# 1_Power.net
KiCad netlist of a schematic drawn in Altium Designer
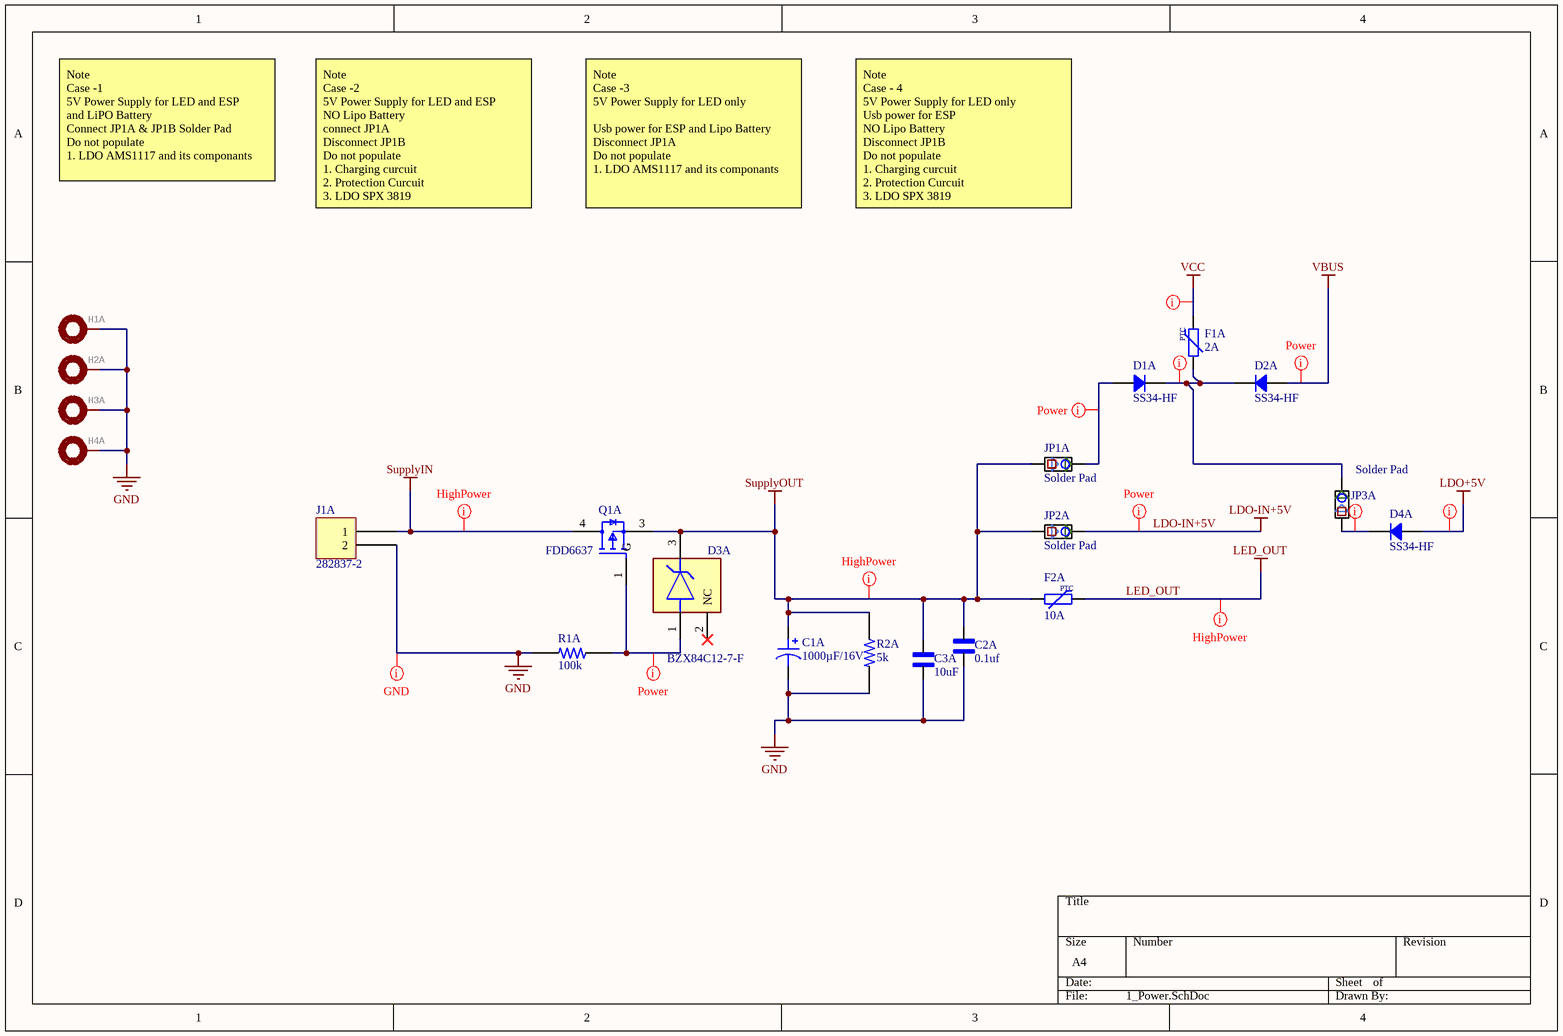
[diagram p0: 1_Power.SchDoc]

(export (version "E")
  (design (tool "Eeschema 10.0.6"))
  (components
    (comp (ref "C1A")
      (value "1000µF/16V")
      (footprint "CAP TH ALUM ELEC D10.00mm S5.00mm H17.50mm")
      (description "AL LYTIC, RADIAL, 16VDC, 1000UF")
      (fields
        (field (name "PART NUMBER") "EEU-FK1C102")
        (field (name "MANUFACTURER") "Panasonic Electronic Components")
      )
      (libsource (lib "ESP-12F_WLED_IOT_LIPO") (part "Polarised Capacitor"))
    )
    (comp (ref "C2A")
      (value "0.1uf")
      (footprint "C-0603")
      (description "Ceramic Capacitor 16V 0603 (1608 Metric)")
      (fields (field (name "MP") "C0603C104J4RAC") (field (name "MF") "KEMET"))
      (libsource (lib "ESP-12F_WLED_IOT_LIPO") (part "C-0603"))
    )
    (comp (ref "C3A")
      (value "10uF")
      (footprint "C-0603")
      (description "Ceramic Capacitor 16V 0603 (1608 Metric)")
      (fields (field (name "MP") "C0603C104J4RAC") (field (name "MF") "KEMET"))
      (libsource (lib "ESP-12F_WLED_IOT_LIPO") (part "C-0603"))
    )
    (comp (ref "D1A")
      (value "SS34-HF")
      (footprint "DO214AC SMA")
      (description "DIODE SCHOTTKY 40V 3A DO214AC")
      (fields (field (name "MANUFACTURER") "Comchip Technology"))
      (libsource (lib "ESP-12F_WLED_IOT_LIPO") (part "Diode"))
    )
    (comp (ref "D2A")
      (value "SS34-HF")
      (footprint "DO214AC SMA")
      (description "DIODE SCHOTTKY 40V 3A DO214AC")
      (fields (field (name "MANUFACTURER") "Comchip Technology"))
      (libsource (lib "ESP-12F_WLED_IOT_LIPO") (part "Diode"))
    )
    (comp (ref "D3A")
      (value "BZX84C12-7-F")
      (footprint "FP-SOT23-MFG")
      (description "DIODE ZENER 12V 300MW SOT23-3")
      (fields
        (field (name "OCTOPART") "https://octopart.com/bzx84c12-7-f-diodes+inc.-327696")
        (field (name "MANUFACTURER") "Diodes Inc.")
      )
      (libsource (lib "ESP-12F_WLED_IOT_LIPO") (part "4a6bcd6c75a58f30e1c7f5dd6419ea8"))
    )
    (comp (ref "D4A")
      (value "SS34-HF")
      (footprint "DO214AC SMA")
      (description "DIODE SCHOTTKY 40V 3A DO214AC")
      (fields (field (name "MANUFACTURER") "Comchip Technology"))
      (libsource (lib "ESP-12F_WLED_IOT_LIPO") (part "Diode"))
    )
    (comp (ref "F1A")
      (value "2A")
      (footprint "FUSE_1206")
      (description "Fuse PPTC SMD 1206")
      (libsource (lib "ESP-12F_WLED_IOT_LIPO") (part "FUSE_PPTC_1206"))
    )
    (comp (ref "F2A")
      (value "10A")
      (footprint "FUSE_1206")
      (description "Fuse PPTC SMD 1206")
      (libsource (lib "ESP-12F_WLED_IOT_LIPO") (part "FUSE_PPTC_1206"))
    )
    (comp (ref "H1A")
      (value "MOUNTING PAD, round")
      (footprint "2,4-PAD")
      (libsource (lib "ESP-12F_WLED_IOT_LIPO") (part "MOUNT-PAD-ROUND2.4"))
    )
    (comp (ref "H2A")
      (value "MOUNTING PAD, round")
      (footprint "2,4-PAD")
      (libsource (lib "ESP-12F_WLED_IOT_LIPO") (part "MOUNT-PAD-ROUND2.4"))
    )
    (comp (ref "H3A")
      (value "MOUNTING PAD, round")
      (footprint "2,4-PAD")
      (libsource (lib "ESP-12F_WLED_IOT_LIPO") (part "MOUNT-PAD-ROUND2.4"))
    )
    (comp (ref "H4A")
      (value "MOUNTING PAD, round")
      (footprint "2,4-PAD")
      (libsource (lib "ESP-12F_WLED_IOT_LIPO") (part "MOUNT-PAD-ROUND2.4"))
    )
    (comp (ref "J1A")
      (value "282837-2")
      (footprint "TE 282837-2")
      (description "TERM BLK 2P SIDE ENT 5.08MM PCB")
      (fields (field (name "MANUFACTURER") "TE Connectivity AMP Connectors") (field (name "VOLTAGE") "300 V"))
      (libsource (lib "ESP-12F_WLED_IOT_LIPO") (part "2 Pin"))
    )
    (comp (ref "JP1A")
      (value "Solder Pad")
      (footprint "Solder_Pad_2_Pin_NC_Medium")
      (description "Solder Pad 2 Pin NC 1.016 mm Pitch")
      (libsource (lib "ESP-12F_WLED_IOT_LIPO") (part "Solder_Pad_2_Pin_NC_Medium"))
    )
    (comp (ref "JP2A")
      (value "Solder Pad")
      (footprint "Solder_Pad_2_Pin_NC_Medium")
      (description "Solder Pad 2 Pin NC 1.016 mm Pitch")
      (libsource (lib "ESP-12F_WLED_IOT_LIPO") (part "Solder_Pad_2_Pin_NC_Medium"))
    )
    (comp (ref "JP3A")
      (value "Solder Pad")
      (footprint "Solder_Pad_2_Pin_NC_Medium")
      (description "Solder Pad 2 Pin NC 1.016 mm Pitch")
      (libsource (lib "ESP-12F_WLED_IOT_LIPO") (part "Solder_Pad_2_Pin_NC_Medium"))
    )
    (comp (ref "Q1A")
      (value "FDD6637")
      (footprint "FP-369AS-MFG")
      (description "MOSFET P-CH 35V 13A DPAK")
      (fields
        (field (name "OCTOPART") "https://octopart.com/fdd6637-on+semiconductor-84325825")
        (field (name "MANUFACTURER") "ON Semiconductor")
      )
      (libsource (lib "ESP-12F_WLED_IOT_LIPO") (part "cee2e0b37b8b7601ebfb19aba2d2b4e"))
    )
    (comp (ref "R1A")
      (value "100k")
      (footprint "R-0603")
      (description "0603")
      (fields (field (name "MP") "2-1623703-0") (field (name "TOLERANCE") "1%"))
      (libsource (lib "ESP-12F_WLED_IOT_LIPO") (part "R-0603"))
    )
    (comp (ref "R2A")
      (value "5k")
      (footprint "R-0603")
      (description "0603")
      (fields (field (name "MP") "2-1623703-0") (field (name "TOLERANCE") "1%"))
      (libsource (lib "ESP-12F_WLED_IOT_LIPO") (part "R-0603"))
    )
  )
  (nets
    (net (code "1") (name "GND") (class "Default")
      (node (ref "C1A") (pin "2") (pinfunction "2_2") (pintype "passive"))
      (node (ref "C2A") (pin "1") (pinfunction "1_1") (pintype "passive"))
      (node (ref "C3A") (pin "1") (pinfunction "1_1") (pintype "passive"))
      (node (ref "H1A") (pin "1") (pinfunction "MOUNT_1") (pintype "passive"))
      (node (ref "H2A") (pin "1") (pinfunction "MOUNT_1") (pintype "passive"))
      (node (ref "H3A") (pin "1") (pinfunction "MOUNT_1") (pintype "passive"))
      (node (ref "H4A") (pin "1") (pinfunction "MOUNT_1") (pintype "passive"))
      (node (ref "J1A") (pin "2") (pinfunction "2_2") (pintype "passive"))
      (node (ref "R1A") (pin "2") (pinfunction "2_2") (pintype "passive"))
      (node (ref "R2A") (pin "2") (pinfunction "2_2") (pintype "passive"))
    )
    (net (code "2") (name "LDO+5V") (class "Default")
      (node (ref "D4A") (pin "1") (pinfunction "1_1") (pintype "passive"))
    )
    (net (code "3") (name "LDO-IN+5V") (class "Default")
      (node (ref "JP2A") (pin "2") (pinfunction "2_2") (pintype "passive"))
    )
    (net (code "4") (name "LED_OUT") (class "Default")
      (node (ref "F2A") (pin "2") (pinfunction "2_2") (pintype "passive"))
    )
    (net (code "5") (name "Net-(D1A-Pad1)") (class "Default")
      (node (ref "D1A") (pin "1") (pinfunction "1_1") (pintype "passive"))
      (node (ref "JP1A") (pin "2") (pinfunction "2_2") (pintype "passive"))
    )
    (net (code "6") (name "Net-(D1A-Pad2)") (class "Default")
      (node (ref "D1A") (pin "2") (pinfunction "2_2") (pintype "passive"))
      (node (ref "D2A") (pin "2") (pinfunction "2_2") (pintype "passive"))
      (node (ref "F1A") (pin "1") (pinfunction "1_1") (pintype "passive"))
      (node (ref "JP3A") (pin "2") (pinfunction "2_2") (pintype "passive"))
    )
    (net (code "7") (name "Net-(D3A-A)") (class "Default")
      (node (ref "D3A") (pin "1") (pinfunction "A_1") (pintype "passive"))
      (node (ref "Q1A") (pin "1") (pinfunction "G_1") (pintype "passive"))
      (node (ref "R1A") (pin "1") (pinfunction "1_1") (pintype "passive"))
    )
    (net (code "8") (name "Net-(D4A-Pad2)") (class "Default")
      (node (ref "D4A") (pin "2") (pinfunction "2_2") (pintype "passive"))
      (node (ref "JP3A") (pin "1") (pinfunction "1_1") (pintype "passive"))
    )
    (net (code "9") (name "SupplyIN") (class "Default")
      (node (ref "J1A") (pin "1") (pinfunction "1_1") (pintype "passive"))
      (node (ref "Q1A") (pin "4") (pinfunction "D_4") (pintype "passive"))
    )
    (net (code "10") (name "SupplyOUT") (class "Default")
      (node (ref "C1A") (pin "1") (pinfunction "1_1") (pintype "passive"))
      (node (ref "C2A") (pin "2") (pinfunction "2_2") (pintype "passive"))
      (node (ref "C3A") (pin "2") (pinfunction "2_2") (pintype "passive"))
      (node (ref "D3A") (pin "3") (pinfunction "C_3") (pintype "passive"))
      (node (ref "F2A") (pin "1") (pinfunction "1_1") (pintype "passive"))
      (node (ref "JP1A") (pin "1") (pinfunction "1_1") (pintype "passive"))
      (node (ref "JP2A") (pin "1") (pinfunction "1_1") (pintype "passive"))
      (node (ref "Q1A") (pin "3") (pinfunction "S_3") (pintype "passive"))
      (node (ref "R2A") (pin "1") (pinfunction "1_1") (pintype "passive"))
    )
    (net (code "11") (name "VBUS") (class "Default")
      (node (ref "D2A") (pin "1") (pinfunction "1_1") (pintype "passive"))
    )
    (net (code "12") (name "VCC") (class "Default")
      (node (ref "F1A") (pin "2") (pinfunction "2_2") (pintype "passive"))
    )
    (net (code "13") (name "unconnected-(D3A-NC-Pad2)") (class "Default")
      (node (ref "D3A") (pin "2") (pinfunction "NC_2") (pintype "passive+no_connect"))
    )
  )
)
